# 404pcb5v.net
KiCad netlist of a schematic drawn in Altium Designer
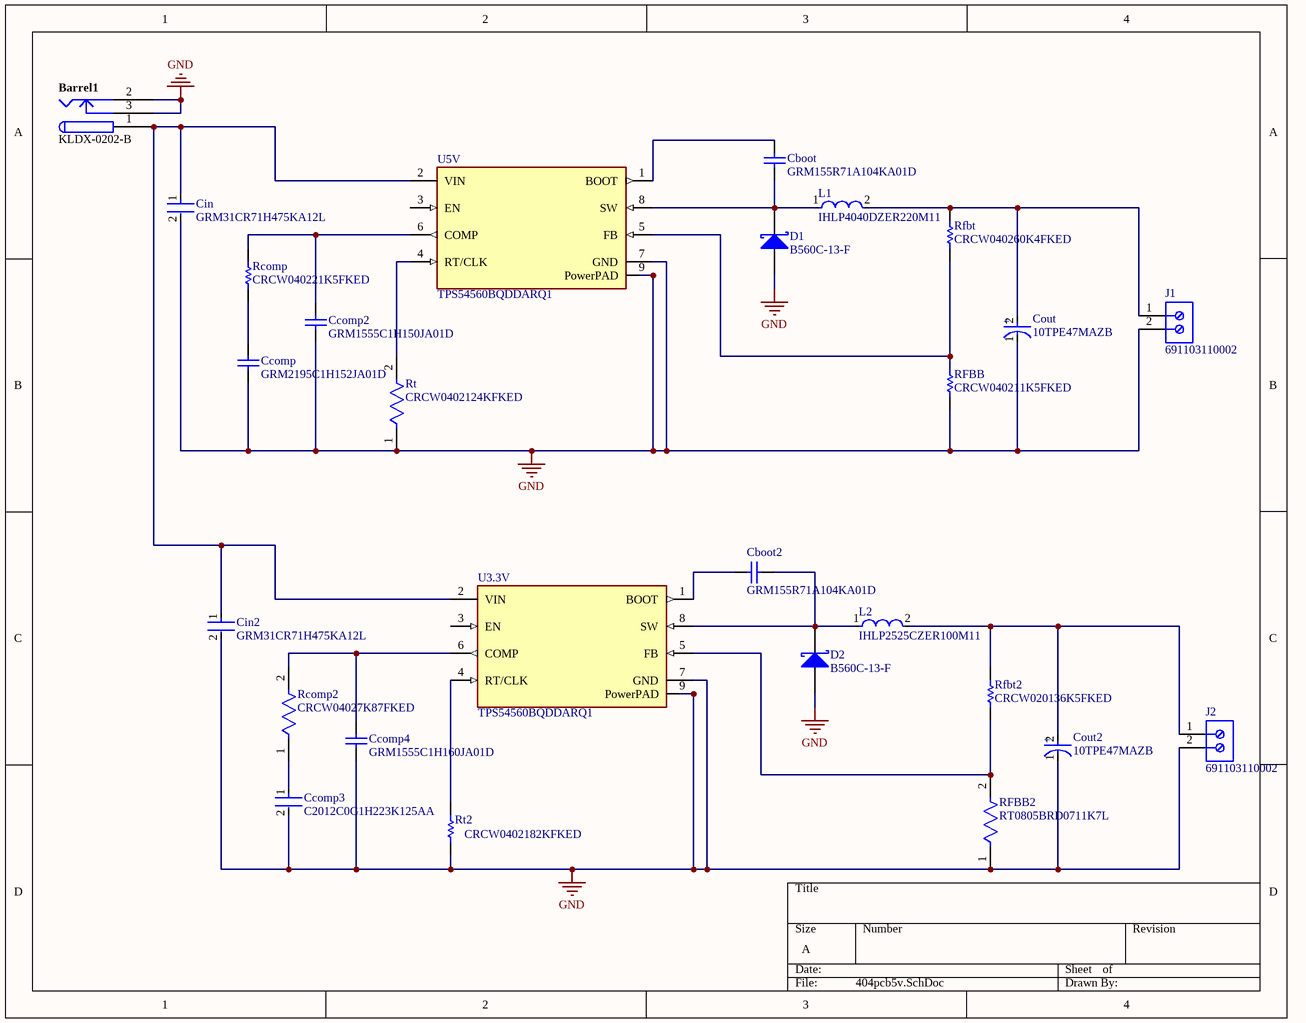
[diagram p0: 404pcb5v.SchDoc]

(export (version "E")
  (design (tool "Eeschema 10.0.6"))
  (components
    (comp (ref "Barrel1")
      (value "KLDX-0202-B")
      (footprint "KYCN-KLDX-0202-B_V")
      (description "3 Conductor Power Jack, 2 break 2 aux contacts")
      (libsource (lib "Altium Content Vault") (part "KYCN-KLDX-0202-B-3"))
    )
    (comp (ref "Cboot")
      (value "GRM155R71A104KA01D")
      (footprint "CAPC1005X55X25LL05T10")
      (description "Chip Capacitor, 0.1 uF, +/- 10%, 10 V, -55 to 125 degC, 0402 (1005 Metric), RoHS, Tape and Reel")
      (fields (field (name "MANUFACTURER") "Murata"))
      (libsource (lib "Altium Content Vault") (part "CAP-NP-2"))
    )
    (comp (ref "Cboot2")
      (value "GRM155R71A104KA01D")
      (footprint "CAPC1005X55X25LL05T10")
      (description "Chip Capacitor, 0.1 uF, +/- 10%, 10 V, -55 to 125 degC, 0402 (1005 Metric), RoHS, Tape and Reel")
      (fields (field (name "MANUFACTURER") "Murata"))
      (libsource (lib "Altium Content Vault") (part "CAP-NP-2"))
    )
    (comp (ref "Ccomp")
      (value "GRM2195C1H152JA01D")
      (footprint "CAPC2013X95X45LL10T25")
      (fields (field (name "MANUFACTURER") "Murata"))
      (libsource (lib "Altium Content Vault") (part "CAP"))
    )
    (comp (ref "Ccomp2")
      (value "GRM1555C1H150JA01D")
      (footprint "CAPC1005X55X25LL05T10")
      (fields (field (name "MANUFACTURER") "Murata"))
      (libsource (lib "Altium Content Vault") (part "CAP"))
    )
    (comp (ref "Ccomp3")
      (value "C2012C0G1H223K125AA")
      (footprint "FP-C2012-125-0_2-IPC_A")
      (description "Multilayer Ceramic Capacitors 22nF ±10% 50V C0G SMD 0805")
      (fields (field (name "TOLERANCE") "10%"))
      (libsource (lib "Altium Content Vault") (part "b4654b650e69147ec39a6b967a45e02"))
    )
    (comp (ref "Ccomp4")
      (value "GRM1555C1H160JA01D")
      (footprint "CAPC1005X55X25NL05T10")
      (fields (field (name "MANUFACTURER") "Murata"))
      (libsource (lib "Altium Content Vault") (part "CAP"))
    )
    (comp (ref "Cin")
      (value "GRM31CR71H475KA12L")
      (footprint "FP-GRM31C-0_2-e0_3_0_8-IPC_C")
      (description "Chip Multilayer Ceramic Capacitors for General Purpose, 1206, 4.7uF, X7R, 15%, 10%, 50V")
      (fields (field (name "VOLTAGE") "50V") (field (name "TOLERANCE") "10%"))
      (libsource (lib "Altium Content Vault") (part "02cd4be3c70576c341d710602a673aa"))
    )
    (comp (ref "Cin2")
      (value "GRM31CR71H475KA12L")
      (footprint "FP-GRM31C-0_2-e0_3_0_8-IPC_C")
      (description "Chip Multilayer Ceramic Capacitors for General Purpose, 1206, 4.7uF, X7R, 15%, 10%, 50V")
      (fields (field (name "VOLTAGE") "50V") (field (name "TOLERANCE") "10%"))
      (libsource (lib "Altium Content Vault") (part "02cd4be3c70576c341d710602a673aa"))
    )
    (comp (ref "Cout")
      (value "10TPE47MAZB")
      (footprint "FP-POSCAP-B2-MFG")
      (description "Molded Tantalum Polymer Capacitor 47uF 20% 10V life 1000Hours SMD 1411")
      (fields (field (name "VOLTAGE") "10V") (field (name "TOLERANCE") "20%"))
      (libsource (lib "Altium Content Vault") (part "cf48714ba7e38822c1575c7ec0b6d1f"))
    )
    (comp (ref "Cout2")
      (value "10TPE47MAZB")
      (footprint "FP-POSCAP-B2-MFG")
      (description "Molded Tantalum Polymer Capacitor 47uF 20% 10V life 1000Hours SMD 1411")
      (fields (field (name "VOLTAGE") "10V") (field (name "TOLERANCE") "20%"))
      (libsource (lib "Altium Content Vault") (part "cf48714ba7e38822c1575c7ec0b6d1f"))
    )
    (comp (ref "D1")
      (value "B560C-13-F")
      (footprint "DIOD-B5X0C-2_M")
      (description "Schottky Barrier Rectifier, 5 A, 60 V, -55 to 125 degC, 2-Pin SMD, RoHS, Tape and Reel")
      (fields (field (name "MANUFACTURER") "DiodesIncorporated"))
      (libsource (lib "Altium Content Vault") (part "DSKY-KA-2"))
    )
    (comp (ref "D2")
      (value "B560C-13-F")
      (footprint "DIOD-B5X0C-2_M")
      (description "Schottky Barrier Rectifier, 5 A, 60 V, -55 to 125 degC, 2-Pin SMD, RoHS, Tape and Reel")
      (fields (field (name "MANUFACTURER") "DiodesIncorporated"))
      (libsource (lib "Altium Content Vault") (part "DSKY-KA-2"))
    )
    (comp (ref "J1")
      (value "691103110002")
      (footprint "691103110002")
      (fields (field (name "VOLTAGE") "125V"))
      (libsource (lib "Altium Content Vault") (part "TBL - 1R - 02P - Screw"))
    )
    (comp (ref "J2")
      (value "691103110002")
      (footprint "691103110002")
      (fields (field (name "VOLTAGE") "125V"))
      (libsource (lib "Altium Content Vault") (part "TBL - 1R - 02P - Screw"))
    )
    (comp (ref "L1")
      (value "IHLP4040DZER220M11")
      (footprint "FP-IHLP-4040DZ-FP_3_124x3-MFG")
      (description "Commercial Inductors, Low DCR Series 22uH 5A 66mΩ 20%")
      (fields (field (name "TOLERANCE") "20%"))
      (libsource (lib "Altium Content Vault") (part "725321dda6339637d4d059423bc1c3c"))
    )
    (comp (ref "L2")
      (value "IHLP2525CZER100M11")
      (footprint "FP-IHLP-2525CZ-FP_2_413x3-MFG")
      (description "Commercial Inductors, Low DCR Series 10uH 4A 71.2mΩ 20%")
      (fields (field (name "TOLERANCE") "20%"))
      (libsource (lib "Altium Content Vault") (part "725321dda6339637d4d059423bc1c3c"))
    )
    (comp (ref "Rcomp")
      (value "CRCW040221K5FKED")
      (footprint "RESC1005X40X25LL05T05")
      (fields (field (name "MANUFACTURER") "Vishay Dale"))
      (libsource (lib "Altium Content Vault") (part "RES"))
    )
    (comp (ref "Rcomp2")
      (value "CRCW04027K87FKED")
      (footprint "FP-CRCW0402-e3-MFG")
      (description "RES Thick Film, 7.87kΩ, 1%, 0.063W, 100ppm/°C, 0402")
      (fields (field (name "TOLERANCE") "1%"))
      (libsource (lib "Altium Content Vault") (part "1029c3af85768c4190bb7ad29bc67b5"))
    )
    (comp (ref "RFBB")
      (value "CRCW040211K5FKED")
      (footprint "RESC1005X40X25NL05T05")
      (fields (field (name "MANUFACTURER") "Vishay Dale"))
      (libsource (lib "Altium Content Vault") (part "RES"))
    )
    (comp (ref "RFBB2")
      (value "RT0805BRD0711K7L")
      (footprint "FP-RT0805-MFG")
      (description "RES 11.7K OHM 0.1% 1/8W 0805")
      (fields (field (name "TOLERANCE") "0.1%") (field (name "MANUFACTURER") "Yageo"))
      (libsource (lib "Altium Content Vault") (part "1029c3af85768c4190bb7ad29bc67b5"))
    )
    (comp (ref "Rfbt")
      (value "CRCW040260K4FKED")
      (footprint "RESC1005X40X25NL05T05")
      (fields (field (name "MANUFACTURER") "Vishay Dale"))
      (libsource (lib "Altium Content Vault") (part "RES"))
    )
    (comp (ref "Rfbt2")
      (value "CRCW020136K5FKED")
      (footprint "RESC0603X28X15NL05T05")
      (fields (field (name "MANUFACTURER") "Vishay Dale"))
      (libsource (lib "Altium Content Vault") (part "RES"))
    )
    (comp (ref "Rt")
      (value "CRCW0402124KFKED")
      (footprint "FP-CRCW0402-e3-IPC_C")
      (description "RES Thick Film, 124kΩ, 1%, 0.063W, 100ppm/°C, 0402")
      (fields (field (name "TOLERANCE") "1%"))
      (libsource (lib "Altium Content Vault") (part "1029c3af85768c4190bb7ad29bc67b5"))
    )
    (comp (ref "Rt2")
      (value "CRCW0402182KFKED")
      (footprint "RESC1005X40X25ML05T05")
      (fields (field (name "MANUFACTURER") "Vishay Dale"))
      (libsource (lib "Altium Content Vault") (part "RES"))
    )
    (comp (ref "U3.3V")
      (value "TPS54560BQDDARQ1")
      (footprint "FP-DDA0008E-MFG")
      (description "IC REG BCK SPLIT RAIL ADJ 8SOPWR")
      (libsource (lib "Altium Content Vault") (part "8b87941cbd97d8a8bf838c081ad91bf"))
    )
    (comp (ref "U5V")
      (value "TPS54560BQDDARQ1")
      (footprint "FP-DDA0008E-MFG")
      (description "IC REG BCK SPLIT RAIL ADJ 8SOPWR")
      (libsource (lib "Altium Content Vault") (part "8b87941cbd97d8a8bf838c081ad91bf"))
    )
  )
  (nets
    (net (code "1") (name "GND") (class "Default")
      (node (ref "Barrel1") (pin "2") (pintype "power_in"))
      (node (ref "Barrel1") (pin "3") (pintype "power_in"))
      (node (ref "Ccomp") (pin "1") (pinfunction "1_1") (pintype "passive"))
      (node (ref "Ccomp2") (pin "1") (pinfunction "1_1") (pintype "passive"))
      (node (ref "Ccomp3") (pin "2") (pinfunction "2_2") (pintype "passive"))
      (node (ref "Ccomp4") (pin "1") (pinfunction "1_1") (pintype "passive"))
      (node (ref "Cin") (pin "2") (pinfunction "2_2") (pintype "passive"))
      (node (ref "Cin2") (pin "2") (pinfunction "2_2") (pintype "passive"))
      (node (ref "Cout") (pin "1") (pinfunction "C_1") (pintype "passive"))
      (node (ref "Cout2") (pin "1") (pinfunction "C_1") (pintype "passive"))
      (node (ref "D1") (pin "2") (pinfunction "A_2") (pintype "passive"))
      (node (ref "D2") (pin "2") (pinfunction "A_2") (pintype "passive"))
      (node (ref "J1") (pin "2") (pinfunction "2_2") (pintype "passive"))
      (node (ref "J2") (pin "2") (pinfunction "2_2") (pintype "passive"))
      (node (ref "RFBB") (pin "1") (pinfunction "1_1") (pintype "passive"))
      (node (ref "RFBB2") (pin "1") (pinfunction "1_1") (pintype "passive"))
      (node (ref "Rt") (pin "1") (pinfunction "1_1") (pintype "passive"))
      (node (ref "Rt2") (pin "1") (pinfunction "1_1") (pintype "passive"))
      (node (ref "U3.3V") (pin "7") (pinfunction "GND_7") (pintype "power_in"))
      (node (ref "U3.3V") (pin "9") (pinfunction "PowerPAD_9") (pintype "power_in"))
      (node (ref "U5V") (pin "7") (pinfunction "GND_7") (pintype "power_in"))
      (node (ref "U5V") (pin "9") (pinfunction "PowerPAD_9") (pintype "power_in"))
    )
    (net (code "2") (name "Net-(Ccomp-Pad2)") (class "Default")
      (node (ref "Ccomp") (pin "2") (pinfunction "2_2") (pintype "passive"))
      (node (ref "Rcomp") (pin "1") (pinfunction "1_1") (pintype "passive"))
    )
    (net (code "3") (name "Net-(Ccomp3-Pad1)") (class "Default")
      (node (ref "Ccomp3") (pin "1") (pinfunction "1_1") (pintype "passive"))
      (node (ref "Rcomp2") (pin "1") (pinfunction "1_1") (pintype "passive"))
    )
    (net (code "4") (name "Net-(Cout-A)") (class "Default")
      (node (ref "Cout") (pin "2") (pinfunction "A_2") (pintype "passive"))
      (node (ref "J1") (pin "1") (pinfunction "1_1") (pintype "passive"))
      (node (ref "L1") (pin "2") (pinfunction "2_2") (pintype "passive"))
      (node (ref "Rfbt") (pin "2") (pinfunction "2_2") (pintype "passive"))
    )
    (net (code "5") (name "Net-(Cout2-A)") (class "Default")
      (node (ref "Cout2") (pin "2") (pinfunction "A_2") (pintype "passive"))
      (node (ref "J2") (pin "1") (pinfunction "1_1") (pintype "passive"))
      (node (ref "L2") (pin "2") (pinfunction "2_2") (pintype "passive"))
      (node (ref "Rfbt2") (pin "2") (pinfunction "2_2") (pintype "passive"))
    )
    (net (code "6") (name "Net-(D1-K)") (class "Default")
      (node (ref "Cboot") (pin "1") (pinfunction "1_1") (pintype "passive"))
      (node (ref "D1") (pin "1") (pinfunction "K_1") (pintype "passive"))
      (node (ref "L1") (pin "1") (pinfunction "1_1") (pintype "passive"))
      (node (ref "U5V") (pin "8") (pinfunction "SW_8") (pintype "input"))
    )
    (net (code "7") (name "Net-(D2-K)") (class "Default")
      (node (ref "Cboot2") (pin "2") (pinfunction "2_2") (pintype "passive"))
      (node (ref "D2") (pin "1") (pinfunction "K_1") (pintype "passive"))
      (node (ref "L2") (pin "1") (pinfunction "1_1") (pintype "passive"))
      (node (ref "U3.3V") (pin "8") (pinfunction "SW_8") (pintype "input"))
    )
    (net (code "8") (name "Net-(U3.3V-BOOT)") (class "Default")
      (node (ref "Cboot2") (pin "1") (pinfunction "1_1") (pintype "passive"))
      (node (ref "U3.3V") (pin "1") (pinfunction "BOOT_1") (pintype "output"))
    )
    (net (code "9") (name "Net-(U3.3V-COMP)") (class "Default")
      (node (ref "Ccomp4") (pin "2") (pinfunction "2_2") (pintype "passive"))
      (node (ref "Rcomp2") (pin "2") (pinfunction "2_2") (pintype "passive"))
      (node (ref "U3.3V") (pin "6") (pinfunction "COMP_6") (pintype "output"))
    )
    (net (code "10") (name "Net-(U3.3V-FB)") (class "Default")
      (node (ref "RFBB2") (pin "2") (pinfunction "2_2") (pintype "passive"))
      (node (ref "Rfbt2") (pin "1") (pinfunction "1_1") (pintype "passive"))
      (node (ref "U3.3V") (pin "5") (pinfunction "FB_5") (pintype "input"))
    )
    (net (code "11") (name "Net-(U3.3V-RT{slash}CLK)") (class "Default")
      (node (ref "Rt2") (pin "2") (pinfunction "2_2") (pintype "passive"))
      (node (ref "U3.3V") (pin "4") (pinfunction "RT/CLK_4") (pintype "input"))
    )
    (net (code "12") (name "Net-(U3.3V-VIN)") (class "Default")
      (node (ref "Barrel1") (pin "1") (pintype "power_in"))
      (node (ref "Cin") (pin "1") (pinfunction "1_1") (pintype "passive"))
      (node (ref "Cin2") (pin "1") (pinfunction "1_1") (pintype "passive"))
      (node (ref "U3.3V") (pin "2") (pinfunction "VIN_2") (pintype "power_in"))
      (node (ref "U5V") (pin "2") (pinfunction "VIN_2") (pintype "power_in"))
    )
    (net (code "13") (name "Net-(U5V-BOOT)") (class "Default")
      (node (ref "Cboot") (pin "2") (pinfunction "2_2") (pintype "passive"))
      (node (ref "U5V") (pin "1") (pinfunction "BOOT_1") (pintype "output"))
    )
    (net (code "14") (name "Net-(U5V-COMP)") (class "Default")
      (node (ref "Ccomp2") (pin "2") (pinfunction "2_2") (pintype "passive"))
      (node (ref "Rcomp") (pin "2") (pinfunction "2_2") (pintype "passive"))
      (node (ref "U5V") (pin "6") (pinfunction "COMP_6") (pintype "output"))
    )
    (net (code "15") (name "Net-(U5V-FB)") (class "Default")
      (node (ref "RFBB") (pin "2") (pinfunction "2_2") (pintype "passive"))
      (node (ref "Rfbt") (pin "1") (pinfunction "1_1") (pintype "passive"))
      (node (ref "U5V") (pin "5") (pinfunction "FB_5") (pintype "input"))
    )
    (net (code "16") (name "Net-(U5V-RT{slash}CLK)") (class "Default")
      (node (ref "Rt") (pin "2") (pinfunction "2_2") (pintype "passive"))
      (node (ref "U5V") (pin "4") (pinfunction "RT/CLK_4") (pintype "input"))
    )
    (net (code "17") (name "unconnected-(U3.3V-EN-Pad3)") (class "Default")
      (node (ref "U3.3V") (pin "3") (pinfunction "EN_3") (pintype "input"))
    )
    (net (code "18") (name "unconnected-(U5V-EN-Pad3)") (class "Default")
      (node (ref "U5V") (pin "3") (pinfunction "EN_3") (pintype "input"))
    )
  )
)
